# etapa1_suma.net
KiCad netlist of a schematic drawn in Altium Designer
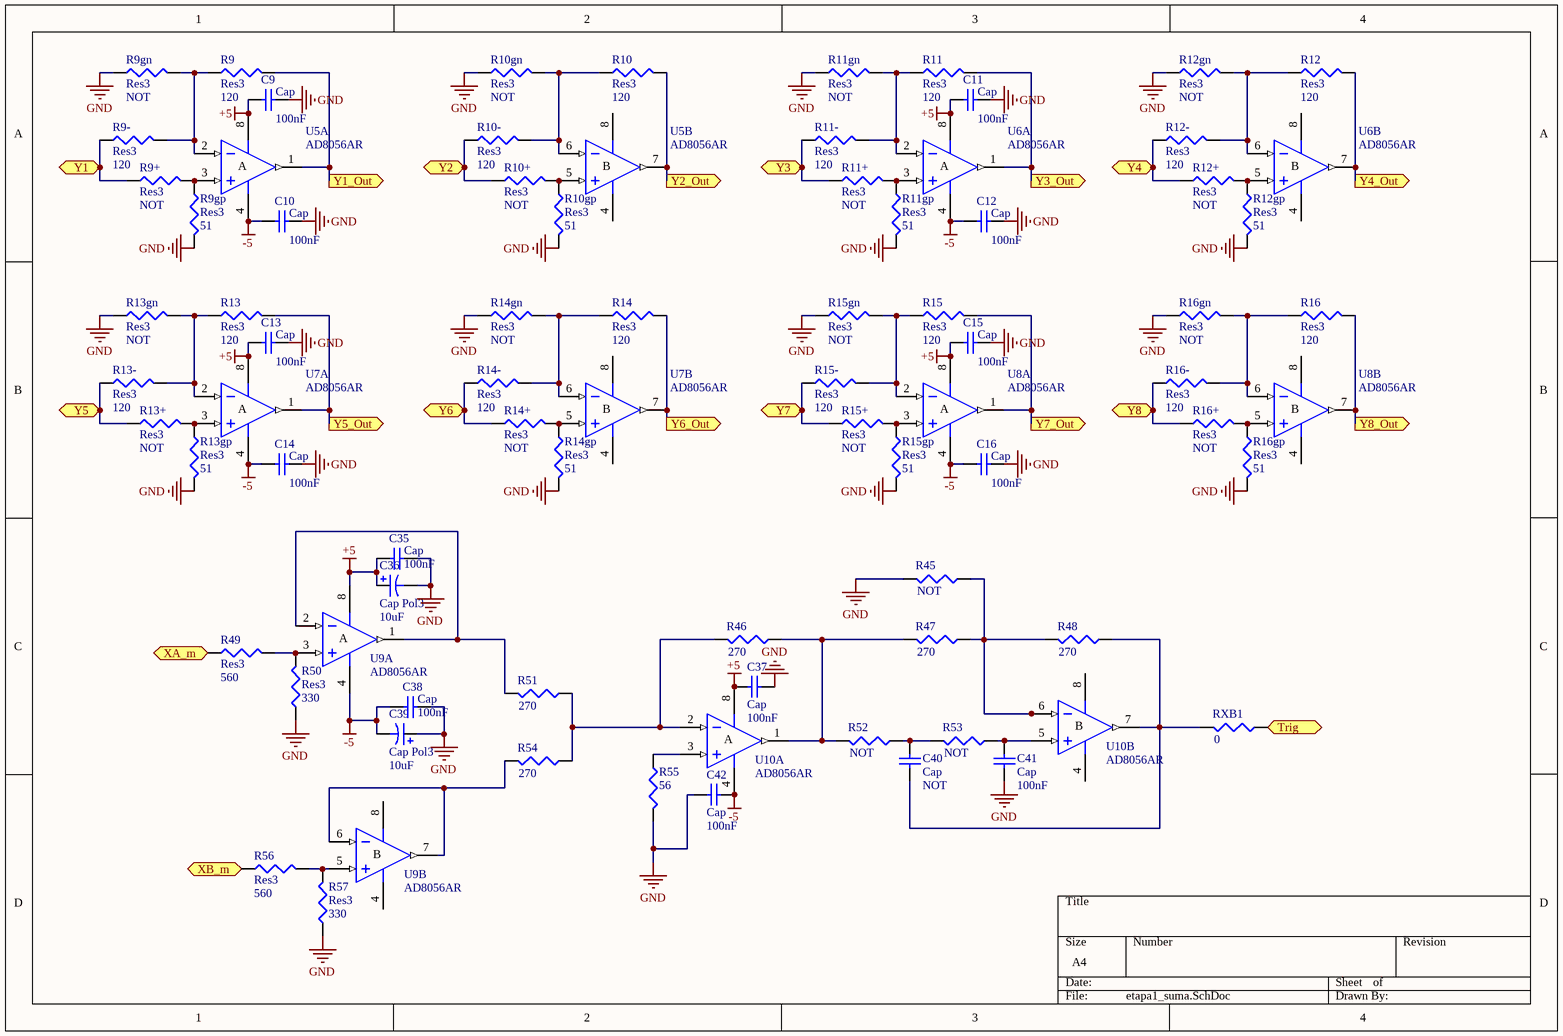
[diagram p0: etapa1_suma.SchDoc]

(export (version "E")
  (design (tool "Eeschema 10.0.6"))
  (components
    (comp (ref "C9")
      (value "Cap")
      (footprint "1608[0603]")
      (description "Capacitor")
      (fields (field (name "ALTIUM_VALUE") "100nF") (field (name "PUBLISHER") "Altium Limited"))
      (libsource (lib "Miscellaneous Devices") (part "Cap"))
    )
    (comp (ref "C10")
      (value "Cap")
      (footprint "1608[0603]")
      (description "Capacitor")
      (fields (field (name "ALTIUM_VALUE") "100nF") (field (name "PUBLISHER") "Altium Limited"))
      (libsource (lib "Miscellaneous Devices") (part "Cap"))
    )
    (comp (ref "C11")
      (value "Cap")
      (footprint "1608[0603]")
      (description "Capacitor")
      (fields (field (name "ALTIUM_VALUE") "100nF") (field (name "PUBLISHER") "Altium Limited"))
      (libsource (lib "Miscellaneous Devices") (part "Cap"))
    )
    (comp (ref "C12")
      (value "Cap")
      (footprint "1608[0603]")
      (description "Capacitor")
      (fields (field (name "ALTIUM_VALUE") "100nF") (field (name "PUBLISHER") "Altium Limited"))
      (libsource (lib "Miscellaneous Devices") (part "Cap"))
    )
    (comp (ref "C13")
      (value "Cap")
      (footprint "1608[0603]")
      (description "Capacitor")
      (fields (field (name "ALTIUM_VALUE") "100nF") (field (name "PUBLISHER") "Altium Limited"))
      (libsource (lib "Miscellaneous Devices") (part "Cap"))
    )
    (comp (ref "C14")
      (value "Cap")
      (footprint "1608[0603]")
      (description "Capacitor")
      (fields (field (name "ALTIUM_VALUE") "100nF") (field (name "PUBLISHER") "Altium Limited"))
      (libsource (lib "Miscellaneous Devices") (part "Cap"))
    )
    (comp (ref "C15")
      (value "Cap")
      (footprint "1608[0603]")
      (description "Capacitor")
      (fields (field (name "ALTIUM_VALUE") "100nF") (field (name "PUBLISHER") "Altium Limited"))
      (libsource (lib "Miscellaneous Devices") (part "Cap"))
    )
    (comp (ref "C16")
      (value "Cap")
      (footprint "1608[0603]")
      (description "Capacitor")
      (fields (field (name "ALTIUM_VALUE") "100nF") (field (name "PUBLISHER") "Altium Limited"))
      (libsource (lib "Miscellaneous Devices") (part "Cap"))
    )
    (comp (ref "C35")
      (value "Cap")
      (footprint "6-0805_N")
      (description "Capacitor")
      (fields (field (name "ALTIUM_VALUE") "100nF") (field (name "PUBLISHER") "Altium Limited"))
      (libsource (lib "Miscellaneous Devices") (part "Cap"))
    )
    (comp (ref "C36")
      (value "Cap Pol3")
      (footprint "6-0805_N")
      (description "Polarized Capacitor (Surface Mount)")
      (fields (field (name "ALTIUM_VALUE") "10uF") (field (name "PUBLISHER") "Altium Limited"))
      (libsource (lib "Miscellaneous Devices") (part "Cap Pol3"))
    )
    (comp (ref "C37")
      (value "Cap")
      (footprint "1608[0603]")
      (description "Capacitor")
      (fields (field (name "ALTIUM_VALUE") "100nF") (field (name "PUBLISHER") "Altium Limited"))
      (libsource (lib "Miscellaneous Devices") (part "Cap"))
    )
    (comp (ref "C38")
      (value "Cap")
      (footprint "6-0805_N")
      (description "Capacitor")
      (fields (field (name "ALTIUM_VALUE") "100nF") (field (name "PUBLISHER") "Altium Limited"))
      (libsource (lib "Miscellaneous Devices") (part "Cap"))
    )
    (comp (ref "C39")
      (value "Cap Pol3")
      (footprint "6-0805_N")
      (description "Polarized Capacitor (Surface Mount)")
      (fields (field (name "ALTIUM_VALUE") "10uF") (field (name "PUBLISHER") "Altium Limited"))
      (libsource (lib "Miscellaneous Devices") (part "Cap Pol3"))
    )
    (comp (ref "C40")
      (value "Cap")
      (footprint "1608[0603]")
      (description "Capacitor")
      (fields (field (name "ALTIUM_VALUE") "NOT") (field (name "PUBLISHER") "Altium Limited"))
      (libsource (lib "Miscellaneous Devices") (part "Cap"))
    )
    (comp (ref "C41")
      (value "Cap")
      (footprint "1608[0603]")
      (description "Capacitor")
      (fields (field (name "ALTIUM_VALUE") "100nF") (field (name "PUBLISHER") "Altium Limited"))
      (libsource (lib "Miscellaneous Devices") (part "Cap"))
    )
    (comp (ref "C42")
      (value "Cap")
      (footprint "1608[0603]")
      (description "Capacitor")
      (fields (field (name "ALTIUM_VALUE") "100nF") (field (name "PUBLISHER") "Altium Limited"))
      (libsource (lib "Miscellaneous Devices") (part "Cap"))
    )
    (comp (ref "R9")
      (value "Res3")
      (footprint "0402")
      (description "Resistor")
      (fields (field (name "ALTIUM_VALUE") "120") (field (name "PUBLISHER") "Altium Limited"))
      (libsource (lib "Miscellaneous Devices") (part "Res3"))
    )
    (comp (ref "R9+")
      (value "Res3")
      (footprint "0402")
      (description "Resistor")
      (fields (field (name "ALTIUM_VALUE") "NOT") (field (name "PUBLISHER") "Altium Limited"))
      (libsource (lib "Miscellaneous Devices") (part "Res3"))
    )
    (comp (ref "R9-")
      (value "Res3")
      (footprint "0402")
      (description "Resistor")
      (fields (field (name "ALTIUM_VALUE") "120") (field (name "PUBLISHER") "Altium Limited"))
      (libsource (lib "Miscellaneous Devices") (part "Res3"))
    )
    (comp (ref "R9gn")
      (value "Res3")
      (footprint "0402")
      (description "Resistor")
      (fields (field (name "ALTIUM_VALUE") "NOT") (field (name "PUBLISHER") "Altium Limited"))
      (libsource (lib "Miscellaneous Devices") (part "Res3"))
    )
    (comp (ref "R9gp")
      (value "Res3")
      (footprint "0402")
      (description "Resistor")
      (fields (field (name "ALTIUM_VALUE") "51") (field (name "PUBLISHER") "Altium Limited"))
      (libsource (lib "Miscellaneous Devices") (part "Res3"))
    )
    (comp (ref "R10")
      (value "Res3")
      (footprint "0402")
      (description "Resistor")
      (fields (field (name "ALTIUM_VALUE") "120") (field (name "PUBLISHER") "Altium Limited"))
      (libsource (lib "Miscellaneous Devices") (part "Res3"))
    )
    (comp (ref "R10+")
      (value "Res3")
      (footprint "0402")
      (description "Resistor")
      (fields (field (name "ALTIUM_VALUE") "NOT") (field (name "PUBLISHER") "Altium Limited"))
      (libsource (lib "Miscellaneous Devices") (part "Res3"))
    )
    (comp (ref "R10-")
      (value "Res3")
      (footprint "0402")
      (description "Resistor")
      (fields (field (name "ALTIUM_VALUE") "120") (field (name "PUBLISHER") "Altium Limited"))
      (libsource (lib "Miscellaneous Devices") (part "Res3"))
    )
    (comp (ref "R10gn")
      (value "Res3")
      (footprint "0402")
      (description "Resistor")
      (fields (field (name "ALTIUM_VALUE") "NOT") (field (name "PUBLISHER") "Altium Limited"))
      (libsource (lib "Miscellaneous Devices") (part "Res3"))
    )
    (comp (ref "R10gp")
      (value "Res3")
      (footprint "0402")
      (description "Resistor")
      (fields (field (name "ALTIUM_VALUE") "51") (field (name "PUBLISHER") "Altium Limited"))
      (libsource (lib "Miscellaneous Devices") (part "Res3"))
    )
    (comp (ref "R11")
      (value "Res3")
      (footprint "0402")
      (description "Resistor")
      (fields (field (name "ALTIUM_VALUE") "120") (field (name "PUBLISHER") "Altium Limited"))
      (libsource (lib "Miscellaneous Devices") (part "Res3"))
    )
    (comp (ref "R11+")
      (value "Res3")
      (footprint "0402")
      (description "Resistor")
      (fields (field (name "ALTIUM_VALUE") "NOT") (field (name "PUBLISHER") "Altium Limited"))
      (libsource (lib "Miscellaneous Devices") (part "Res3"))
    )
    (comp (ref "R11-")
      (value "Res3")
      (footprint "0402")
      (description "Resistor")
      (fields (field (name "ALTIUM_VALUE") "120") (field (name "PUBLISHER") "Altium Limited"))
      (libsource (lib "Miscellaneous Devices") (part "Res3"))
    )
    (comp (ref "R11gn")
      (value "Res3")
      (footprint "0402")
      (description "Resistor")
      (fields (field (name "ALTIUM_VALUE") "NOT") (field (name "PUBLISHER") "Altium Limited"))
      (libsource (lib "Miscellaneous Devices") (part "Res3"))
    )
    (comp (ref "R11gp")
      (value "Res3")
      (footprint "0402")
      (description "Resistor")
      (fields (field (name "ALTIUM_VALUE") "51") (field (name "PUBLISHER") "Altium Limited"))
      (libsource (lib "Miscellaneous Devices") (part "Res3"))
    )
    (comp (ref "R12")
      (value "Res3")
      (footprint "0402")
      (description "Resistor")
      (fields (field (name "ALTIUM_VALUE") "120") (field (name "PUBLISHER") "Altium Limited"))
      (libsource (lib "Miscellaneous Devices") (part "Res3"))
    )
    (comp (ref "R12+")
      (value "Res3")
      (footprint "0402")
      (description "Resistor")
      (fields (field (name "ALTIUM_VALUE") "NOT") (field (name "PUBLISHER") "Altium Limited"))
      (libsource (lib "Miscellaneous Devices") (part "Res3"))
    )
    (comp (ref "R12-")
      (value "Res3")
      (footprint "0402")
      (description "Resistor")
      (fields (field (name "ALTIUM_VALUE") "120") (field (name "PUBLISHER") "Altium Limited"))
      (libsource (lib "Miscellaneous Devices") (part "Res3"))
    )
    (comp (ref "R12gn")
      (value "Res3")
      (footprint "0402")
      (description "Resistor")
      (fields (field (name "ALTIUM_VALUE") "NOT") (field (name "PUBLISHER") "Altium Limited"))
      (libsource (lib "Miscellaneous Devices") (part "Res3"))
    )
    (comp (ref "R12gp")
      (value "Res3")
      (footprint "0402")
      (description "Resistor")
      (fields (field (name "ALTIUM_VALUE") "51") (field (name "PUBLISHER") "Altium Limited"))
      (libsource (lib "Miscellaneous Devices") (part "Res3"))
    )
    (comp (ref "R13")
      (value "Res3")
      (footprint "0402")
      (description "Resistor")
      (fields (field (name "ALTIUM_VALUE") "120") (field (name "PUBLISHER") "Altium Limited"))
      (libsource (lib "Miscellaneous Devices") (part "Res3"))
    )
    (comp (ref "R13+")
      (value "Res3")
      (footprint "0402")
      (description "Resistor")
      (fields (field (name "ALTIUM_VALUE") "NOT") (field (name "PUBLISHER") "Altium Limited"))
      (libsource (lib "Miscellaneous Devices") (part "Res3"))
    )
    (comp (ref "R13-")
      (value "Res3")
      (footprint "0402")
      (description "Resistor")
      (fields (field (name "ALTIUM_VALUE") "120") (field (name "PUBLISHER") "Altium Limited"))
      (libsource (lib "Miscellaneous Devices") (part "Res3"))
    )
    (comp (ref "R13gn")
      (value "Res3")
      (footprint "0402")
      (description "Resistor")
      (fields (field (name "ALTIUM_VALUE") "NOT") (field (name "PUBLISHER") "Altium Limited"))
      (libsource (lib "Miscellaneous Devices") (part "Res3"))
    )
    (comp (ref "R13gp")
      (value "Res3")
      (footprint "0402")
      (description "Resistor")
      (fields (field (name "ALTIUM_VALUE") "51") (field (name "PUBLISHER") "Altium Limited"))
      (libsource (lib "Miscellaneous Devices") (part "Res3"))
    )
    (comp (ref "R14")
      (value "Res3")
      (footprint "0402")
      (description "Resistor")
      (fields (field (name "ALTIUM_VALUE") "120") (field (name "PUBLISHER") "Altium Limited"))
      (libsource (lib "Miscellaneous Devices") (part "Res3"))
    )
    (comp (ref "R14+")
      (value "Res3")
      (footprint "0402")
      (description "Resistor")
      (fields (field (name "ALTIUM_VALUE") "NOT") (field (name "PUBLISHER") "Altium Limited"))
      (libsource (lib "Miscellaneous Devices") (part "Res3"))
    )
    (comp (ref "R14-")
      (value "Res3")
      (footprint "0402")
      (description "Resistor")
      (fields (field (name "ALTIUM_VALUE") "120") (field (name "PUBLISHER") "Altium Limited"))
      (libsource (lib "Miscellaneous Devices") (part "Res3"))
    )
    (comp (ref "R14gn")
      (value "Res3")
      (footprint "0402")
      (description "Resistor")
      (fields (field (name "ALTIUM_VALUE") "NOT") (field (name "PUBLISHER") "Altium Limited"))
      (libsource (lib "Miscellaneous Devices") (part "Res3"))
    )
    (comp (ref "R14gp")
      (value "Res3")
      (footprint "0402")
      (description "Resistor")
      (fields (field (name "ALTIUM_VALUE") "51") (field (name "PUBLISHER") "Altium Limited"))
      (libsource (lib "Miscellaneous Devices") (part "Res3"))
    )
    (comp (ref "R15")
      (value "Res3")
      (footprint "0402")
      (description "Resistor")
      (fields (field (name "ALTIUM_VALUE") "120") (field (name "PUBLISHER") "Altium Limited"))
      (libsource (lib "Miscellaneous Devices") (part "Res3"))
    )
    (comp (ref "R15+")
      (value "Res3")
      (footprint "0402")
      (description "Resistor")
      (fields (field (name "ALTIUM_VALUE") "NOT") (field (name "PUBLISHER") "Altium Limited"))
      (libsource (lib "Miscellaneous Devices") (part "Res3"))
    )
    (comp (ref "R15-")
      (value "Res3")
      (footprint "0402")
      (description "Resistor")
      (fields (field (name "ALTIUM_VALUE") "120") (field (name "PUBLISHER") "Altium Limited"))
      (libsource (lib "Miscellaneous Devices") (part "Res3"))
    )
    (comp (ref "R15gn")
      (value "Res3")
      (footprint "0402")
      (description "Resistor")
      (fields (field (name "ALTIUM_VALUE") "NOT") (field (name "PUBLISHER") "Altium Limited"))
      (libsource (lib "Miscellaneous Devices") (part "Res3"))
    )
    (comp (ref "R15gp")
      (value "Res3")
      (footprint "0402")
      (description "Resistor")
      (fields (field (name "ALTIUM_VALUE") "51") (field (name "PUBLISHER") "Altium Limited"))
      (libsource (lib "Miscellaneous Devices") (part "Res3"))
    )
    (comp (ref "R16")
      (value "Res3")
      (footprint "0402")
      (description "Resistor")
      (fields (field (name "ALTIUM_VALUE") "120") (field (name "PUBLISHER") "Altium Limited"))
      (libsource (lib "Miscellaneous Devices") (part "Res3"))
    )
    (comp (ref "R16+")
      (value "Res3")
      (footprint "0402")
      (description "Resistor")
      (fields (field (name "ALTIUM_VALUE") "NOT") (field (name "PUBLISHER") "Altium Limited"))
      (libsource (lib "Miscellaneous Devices") (part "Res3"))
    )
    (comp (ref "R16-")
      (value "Res3")
      (footprint "0402")
      (description "Resistor")
      (fields (field (name "ALTIUM_VALUE") "120") (field (name "PUBLISHER") "Altium Limited"))
      (libsource (lib "Miscellaneous Devices") (part "Res3"))
    )
    (comp (ref "R16gn")
      (value "Res3")
      (footprint "0402")
      (description "Resistor")
      (fields (field (name "ALTIUM_VALUE") "NOT") (field (name "PUBLISHER") "Altium Limited"))
      (libsource (lib "Miscellaneous Devices") (part "Res3"))
    )
    (comp (ref "R16gp")
      (value "Res3")
      (footprint "0402")
      (description "Resistor")
      (fields (field (name "ALTIUM_VALUE") "51") (field (name "PUBLISHER") "Altium Limited"))
      (libsource (lib "Miscellaneous Devices") (part "Res3"))
    )
    (comp (ref "R45")
      (value "NOT")
      (footprint "J1-0603")
      (description "Resistor")
      (fields (field (name "Comment") "Res3") (field (name "PUBLISHER") "Altium Limited"))
      (libsource (lib "Miscellaneous Devices") (part "Res3"))
    )
    (comp (ref "R46")
      (value "270")
      (footprint "J1-0603")
      (description "Resistor")
      (fields (field (name "Comment") "Res3") (field (name "PUBLISHER") "Altium Limited"))
      (libsource (lib "Miscellaneous Devices") (part "Res3"))
    )
    (comp (ref "R47")
      (value "270")
      (footprint "J1-0603")
      (description "Resistor")
      (fields (field (name "Comment") "Res3") (field (name "PUBLISHER") "Altium Limited"))
      (libsource (lib "Miscellaneous Devices") (part "Res3"))
    )
    (comp (ref "R48")
      (value "270")
      (footprint "J1-0603")
      (description "Resistor")
      (fields (field (name "Comment") "Res3") (field (name "PUBLISHER") "Altium Limited"))
      (libsource (lib "Miscellaneous Devices") (part "Res3"))
    )
    (comp (ref "R49")
      (value "Res3")
      (footprint "J1-0603")
      (description "Resistor")
      (fields (field (name "ALTIUM_VALUE") "560") (field (name "PUBLISHER") "Altium Limited"))
      (libsource (lib "Miscellaneous Devices") (part "Res3"))
    )
    (comp (ref "R50")
      (value "Res3")
      (footprint "J1-0603")
      (description "Resistor")
      (fields (field (name "ALTIUM_VALUE") "330") (field (name "PUBLISHER") "Altium Limited"))
      (libsource (lib "Miscellaneous Devices") (part "Res3"))
    )
    (comp (ref "R51")
      (value "270")
      (footprint "J1-0603")
      (description "Resistor")
      (fields (field (name "Comment") "Res3") (field (name "PUBLISHER") "Altium Limited"))
      (libsource (lib "Miscellaneous Devices") (part "Res3"))
    )
    (comp (ref "R52")
      (value "NOT")
      (footprint "J1-0603")
      (description "Resistor")
      (fields (field (name "Comment") "Res3") (field (name "PUBLISHER") "Altium Limited"))
      (libsource (lib "Miscellaneous Devices") (part "Res3"))
    )
    (comp (ref "R53")
      (value "NOT")
      (footprint "J1-0603")
      (description "Resistor")
      (fields (field (name "Comment") "Res3") (field (name "PUBLISHER") "Altium Limited"))
      (libsource (lib "Miscellaneous Devices") (part "Res3"))
    )
    (comp (ref "R54")
      (value "270")
      (footprint "J1-0603")
      (description "Resistor")
      (fields (field (name "Comment") "Res3") (field (name "PUBLISHER") "Altium Limited"))
      (libsource (lib "Miscellaneous Devices") (part "Res3"))
    )
    (comp (ref "R55")
      (value "56")
      (footprint "J1-0603")
      (description "Resistor")
      (fields (field (name "Comment") "Res3") (field (name "PUBLISHER") "Altium Limited"))
      (libsource (lib "Miscellaneous Devices") (part "Res3"))
    )
    (comp (ref "R56")
      (value "Res3")
      (footprint "J1-0603")
      (description "Resistor")
      (fields (field (name "ALTIUM_VALUE") "560") (field (name "PUBLISHER") "Altium Limited"))
      (libsource (lib "Miscellaneous Devices") (part "Res3"))
    )
    (comp (ref "R57")
      (value "Res3")
      (footprint "J1-0603")
      (description "Resistor")
      (fields (field (name "ALTIUM_VALUE") "330") (field (name "PUBLISHER") "Altium Limited"))
      (libsource (lib "Miscellaneous Devices") (part "Res3"))
    )
    (comp (ref "RXB1")
      (value "0")
      (footprint "J1-0603")
      (description "Resistor")
      (fields (field (name "Comment") "Res3") (field (name "PUBLISHER") "Altium Limited"))
      (libsource (lib "Miscellaneous Devices") (part "Res3"))
    )
    (comp (ref "U5")
      (value "AD8056AR")
      (footprint "RM-8")
      (description "Low Cost, 300MHz Voltage Feedback Amplifier")
      (fields (field (name "PUBLISHER") "Altium Limited"))
      (libsource (lib "AD Operational Amplifier") (part "AD8056AR"))
    )
    (comp (ref "U6")
      (value "AD8056AR")
      (footprint "RM-8")
      (description "Low Cost, 300MHz Voltage Feedback Amplifier")
      (fields (field (name "PUBLISHER") "Altium Limited"))
      (libsource (lib "AD Operational Amplifier") (part "AD8056AR"))
    )
    (comp (ref "U7")
      (value "AD8056AR")
      (footprint "RM-8")
      (description "Low Cost, 300MHz Voltage Feedback Amplifier")
      (fields (field (name "PUBLISHER") "Altium Limited"))
      (libsource (lib "AD Operational Amplifier") (part "AD8056AR"))
    )
    (comp (ref "U8")
      (value "AD8056AR")
      (footprint "RM-8")
      (description "Low Cost, 300MHz Voltage Feedback Amplifier")
      (fields (field (name "PUBLISHER") "Altium Limited"))
      (libsource (lib "AD Operational Amplifier") (part "AD8056AR"))
    )
    (comp (ref "U9")
      (value "AD8056AR")
      (footprint "RM-8")
      (description "Low Cost, 300MHz Voltage Feedback Amplifier")
      (fields (field (name "PUBLISHER") "Altium Limited"))
      (libsource (lib "AD Operational Amplifier") (part "AD8056AR"))
    )
    (comp (ref "U10")
      (value "AD8056AR")
      (footprint "RM-8")
      (description "Low Cost, 300MHz Voltage Feedback Amplifier")
      (fields (field (name "PUBLISHER") "Altium Limited"))
      (libsource (lib "AD Operational Amplifier") (part "AD8056AR"))
    )
  )
  (nets
    (net (code "1") (name "+5") (class "Default")
      (node (ref "C11") (pin "2") (pinfunction "2_2") (pintype "passive"))
      (node (ref "C13") (pin "2") (pinfunction "2_2") (pintype "passive"))
      (node (ref "C15") (pin "2") (pinfunction "2_2") (pintype "passive"))
      (node (ref "C35") (pin "2") (pinfunction "2_2") (pintype "passive"))
      (node (ref "C36") (pin "1") (pinfunction "1_1") (pintype "passive"))
      (node (ref "C37") (pin "1") (pinfunction "1_1") (pintype "passive"))
      (node (ref "C9") (pin "2") (pinfunction "2_2") (pintype "passive"))
      (node (ref "U10") (pin "8") (pinfunction "V+_8") (pintype "power_in"))
      (node (ref "U5") (pin "8") (pinfunction "V+_8") (pintype "power_in"))
      (node (ref "U6") (pin "8") (pinfunction "V+_8") (pintype "power_in"))
      (node (ref "U7") (pin "8") (pinfunction "V+_8") (pintype "power_in"))
      (node (ref "U8") (pin "8") (pinfunction "V+_8") (pintype "power_in"))
      (node (ref "U9") (pin "8") (pinfunction "V+_8") (pintype "power_in"))
    )
    (net (code "2") (name "-5") (class "Default")
      (node (ref "C10") (pin "2") (pinfunction "2_2") (pintype "passive"))
      (node (ref "C12") (pin "2") (pinfunction "2_2") (pintype "passive"))
      (node (ref "C14") (pin "2") (pinfunction "2_2") (pintype "passive"))
      (node (ref "C16") (pin "2") (pinfunction "2_2") (pintype "passive"))
      (node (ref "C38") (pin "2") (pinfunction "2_2") (pintype "passive"))
      (node (ref "C39") (pin "2") (pinfunction "2_2") (pintype "passive"))
      (node (ref "C42") (pin "2") (pinfunction "2_2") (pintype "passive"))
      (node (ref "U10") (pin "4") (pinfunction "V-_4") (pintype "power_in"))
      (node (ref "U5") (pin "4") (pinfunction "V-_4") (pintype "power_in"))
      (node (ref "U6") (pin "4") (pinfunction "V-_4") (pintype "power_in"))
      (node (ref "U7") (pin "4") (pinfunction "V-_4") (pintype "power_in"))
      (node (ref "U8") (pin "4") (pinfunction "V-_4") (pintype "power_in"))
      (node (ref "U9") (pin "4") (pinfunction "V-_4") (pintype "power_in"))
    )
    (net (code "3") (name "/Trig") (class "Default")
      (node (ref "RXB1") (pin "1") (pinfunction "1_1") (pintype "passive"))
    )
    (net (code "4") (name "/XA_m") (class "Default")
      (node (ref "R49") (pin "1") (pinfunction "1_1") (pintype "passive"))
    )
    (net (code "5") (name "/XB_m") (class "Default")
      (node (ref "R56") (pin "1") (pinfunction "1_1") (pintype "passive"))
    )
    (net (code "6") (name "/Y1") (class "Default")
      (node (ref "R9+") (pin "1") (pinfunction "1_1") (pintype "passive"))
      (node (ref "R9-") (pin "1") (pinfunction "1_1") (pintype "passive"))
    )
    (net (code "7") (name "/Y1_Out") (class "Default")
      (node (ref "R9") (pin "2") (pinfunction "2_2") (pintype "passive"))
      (node (ref "U5") (pin "1") (pinfunction "OUT_1") (pintype "output"))
    )
    (net (code "8") (name "/Y2") (class "Default")
      (node (ref "R10+") (pin "1") (pinfunction "1_1") (pintype "passive"))
      (node (ref "R10-") (pin "1") (pinfunction "1_1") (pintype "passive"))
    )
    (net (code "9") (name "/Y2_Out") (class "Default")
      (node (ref "R10") (pin "2") (pinfunction "2_2") (pintype "passive"))
      (node (ref "U5") (pin "7") (pinfunction "OUT_7") (pintype "output"))
    )
    (net (code "10") (name "/Y3") (class "Default")
      (node (ref "R11+") (pin "1") (pinfunction "1_1") (pintype "passive"))
      (node (ref "R11-") (pin "1") (pinfunction "1_1") (pintype "passive"))
    )
    (net (code "11") (name "/Y3_Out") (class "Default")
      (node (ref "R11") (pin "2") (pinfunction "2_2") (pintype "passive"))
      (node (ref "U6") (pin "1") (pinfunction "OUT_1") (pintype "output"))
    )
    (net (code "12") (name "/Y4") (class "Default")
      (node (ref "R12+") (pin "1") (pinfunction "1_1") (pintype "passive"))
      (node (ref "R12-") (pin "1") (pinfunction "1_1") (pintype "passive"))
    )
    (net (code "13") (name "/Y4_Out") (class "Default")
      (node (ref "R12") (pin "2") (pinfunction "2_2") (pintype "passive"))
      (node (ref "U6") (pin "7") (pinfunction "OUT_7") (pintype "output"))
    )
    (net (code "14") (name "/Y5") (class "Default")
      (node (ref "R13+") (pin "1") (pinfunction "1_1") (pintype "passive"))
      (node (ref "R13-") (pin "1") (pinfunction "1_1") (pintype "passive"))
    )
    (net (code "15") (name "/Y5_Out") (class "Default")
      (node (ref "R13") (pin "2") (pinfunction "2_2") (pintype "passive"))
      (node (ref "U7") (pin "1") (pinfunction "OUT_1") (pintype "output"))
    )
    (net (code "16") (name "/Y6") (class "Default")
      (node (ref "R14+") (pin "1") (pinfunction "1_1") (pintype "passive"))
      (node (ref "R14-") (pin "1") (pinfunction "1_1") (pintype "passive"))
    )
    (net (code "17") (name "/Y6_Out") (class "Default")
      (node (ref "R14") (pin "2") (pinfunction "2_2") (pintype "passive"))
      (node (ref "U7") (pin "7") (pinfunction "OUT_7") (pintype "output"))
    )
    (net (code "18") (name "/Y7") (class "Default")
      (node (ref "R15+") (pin "1") (pinfunction "1_1") (pintype "passive"))
      (node (ref "R15-") (pin "1") (pinfunction "1_1") (pintype "passive"))
    )
    (net (code "19") (name "/Y7_Out") (class "Default")
      (node (ref "R15") (pin "2") (pinfunction "2_2") (pintype "passive"))
      (node (ref "U8") (pin "1") (pinfunction "OUT_1") (pintype "output"))
    )
    (net (code "20") (name "/Y8") (class "Default")
      (node (ref "R16+") (pin "1") (pinfunction "1_1") (pintype "passive"))
      (node (ref "R16-") (pin "1") (pinfunction "1_1") (pintype "passive"))
    )
    (net (code "21") (name "/Y8_Out") (class "Default")
      (node (ref "R16") (pin "2") (pinfunction "2_2") (pintype "passive"))
      (node (ref "U8") (pin "7") (pinfunction "OUT_7") (pintype "output"))
    )
    (net (code "22") (name "GND") (class "Default")
      (node (ref "C10") (pin "1") (pinfunction "1_1") (pintype "passive"))
      (node (ref "C11") (pin "1") (pinfunction "1_1") (pintype "passive"))
      (node (ref "C12") (pin "1") (pinfunction "1_1") (pintype "passive"))
      (node (ref "C13") (pin "1") (pinfunction "1_1") (pintype "passive"))
      (node (ref "C14") (pin "1") (pinfunction "1_1") (pintype "passive"))
      (node (ref "C15") (pin "1") (pinfunction "1_1") (pintype "passive"))
      (node (ref "C16") (pin "1") (pinfunction "1_1") (pintype "passive"))
      (node (ref "C35") (pin "1") (pinfunction "1_1") (pintype "passive"))
      (node (ref "C36") (pin "2") (pinfunction "2_2") (pintype "passive"))
      (node (ref "C37") (pin "2") (pinfunction "2_2") (pintype "passive"))
      (node (ref "C38") (pin "1") (pinfunction "1_1") (pintype "passive"))
      (node (ref "C39") (pin "1") (pinfunction "1_1") (pintype "passive"))
      (node (ref "C41") (pin "2") (pinfunction "2_2") (pintype "passive"))
      (node (ref "C42") (pin "1") (pinfunction "1_1") (pintype "passive"))
      (node (ref "C9") (pin "1") (pinfunction "1_1") (pintype "passive"))
      (node (ref "R10gn") (pin "1") (pinfunction "1_1") (pintype "passive"))
      (node (ref "R10gp") (pin "2") (pinfunction "2_2") (pintype "passive"))
      (node (ref "R11gn") (pin "1") (pinfunction "1_1") (pintype "passive"))
      (node (ref "R11gp") (pin "2") (pinfunction "2_2") (pintype "passive"))
      (node (ref "R12gn") (pin "1") (pinfunction "1_1") (pintype "passive"))
      (node (ref "R12gp") (pin "2") (pinfunction "2_2") (pintype "passive"))
      (node (ref "R13gn") (pin "1") (pinfunction "1_1") (pintype "passive"))
      (node (ref "R13gp") (pin "2") (pinfunction "2_2") (pintype "passive"))
      (node (ref "R14gn") (pin "1") (pinfunction "1_1") (pintype "passive"))
      (node (ref "R14gp") (pin "2") (pinfunction "2_2") (pintype "passive"))
      (node (ref "R15gn") (pin "1") (pinfunction "1_1") (pintype "passive"))
      (node (ref "R15gp") (pin "2") (pinfunction "2_2") (pintype "passive"))
      (node (ref "R16gn") (pin "1") (pinfunction "1_1") (pintype "passive"))
      (node (ref "R16gp") (pin "2") (pinfunction "2_2") (pintype "passive"))
      (node (ref "R45") (pin "2") (pinfunction "2_2") (pintype "passive"))
      (node (ref "R50") (pin "1") (pinfunction "1_1") (pintype "passive"))
      (node (ref "R55") (pin "2") (pinfunction "2_2") (pintype "passive"))
      (node (ref "R57") (pin "1") (pinfunction "1_1") (pintype "passive"))
      (node (ref "R9gn") (pin "1") (pinfunction "1_1") (pintype "passive"))
      (node (ref "R9gp") (pin "2") (pinfunction "2_2") (pintype "passive"))
    )
    (net (code "23") (name "Net-(C40-Pad1)") (class "Default")
      (node (ref "C40") (pin "1") (pinfunction "1_1") (pintype "passive"))
      (node (ref "R52") (pin "1") (pinfunction "1_1") (pintype "passive"))
      (node (ref "R53") (pin "2") (pinfunction "2_2") (pintype "passive"))
    )
    (net (code "24") (name "Net-(U5A-IN+)") (class "Default")
      (node (ref "R9+") (pin "2") (pinfunction "2_2") (pintype "passive"))
      (node (ref "R9gp") (pin "1") (pinfunction "1_1") (pintype "passive"))
      (node (ref "U5") (pin "3") (pinfunction "IN+_3") (pintype "input"))
    )
    (net (code "25") (name "Net-(U5A-IN-)") (class "Default")
      (node (ref "R9") (pin "1") (pinfunction "1_1") (pintype "passive"))
      (node (ref "R9-") (pin "2") (pinfunction "2_2") (pintype "passive"))
      (node (ref "R9gn") (pin "2") (pinfunction "2_2") (pintype "passive"))
      (node (ref "U5") (pin "2") (pinfunction "IN-_2") (pintype "input"))
    )
    (net (code "26") (name "Net-(U5B-IN+)") (class "Default")
      (node (ref "R10+") (pin "2") (pinfunction "2_2") (pintype "passive"))
      (node (ref "R10gp") (pin "1") (pinfunction "1_1") (pintype "passive"))
      (node (ref "U5") (pin "5") (pinfunction "IN+_5") (pintype "input"))
    )
    (net (code "27") (name "Net-(U5B-IN-)") (class "Default")
      (node (ref "R10") (pin "1") (pinfunction "1_1") (pintype "passive"))
      (node (ref "R10-") (pin "2") (pinfunction "2_2") (pintype "passive"))
      (node (ref "R10gn") (pin "2") (pinfunction "2_2") (pintype "passive"))
      (node (ref "U5") (pin "6") (pinfunction "IN-_6") (pintype "input"))
    )
    (net (code "28") (name "Net-(U6A-IN+)") (class "Default")
      (node (ref "R11+") (pin "2") (pinfunction "2_2") (pintype "passive"))
      (node (ref "R11gp") (pin "1") (pinfunction "1_1") (pintype "passive"))
      (node (ref "U6") (pin "3") (pinfunction "IN+_3") (pintype "input"))
    )
    (net (code "29") (name "Net-(U6A-IN-)") (class "Default")
      (node (ref "R11") (pin "1") (pinfunction "1_1") (pintype "passive"))
      (node (ref "R11-") (pin "2") (pinfunction "2_2") (pintype "passive"))
      (node (ref "R11gn") (pin "2") (pinfunction "2_2") (pintype "passive"))
      (node (ref "U6") (pin "2") (pinfunction "IN-_2") (pintype "input"))
    )
    (net (code "30") (name "Net-(U6B-IN+)") (class "Default")
      (node (ref "R12+") (pin "2") (pinfunction "2_2") (pintype "passive"))
      (node (ref "R12gp") (pin "1") (pinfunction "1_1") (pintype "passive"))
      (node (ref "U6") (pin "5") (pinfunction "IN+_5") (pintype "input"))
    )
    (net (code "31") (name "Net-(U6B-IN-)") (class "Default")
      (node (ref "R12") (pin "1") (pinfunction "1_1") (pintype "passive"))
      (node (ref "R12-") (pin "2") (pinfunction "2_2") (pintype "passive"))
      (node (ref "R12gn") (pin "2") (pinfunction "2_2") (pintype "passive"))
      (node (ref "U6") (pin "6") (pinfunction "IN-_6") (pintype "input"))
    )
    (net (code "32") (name "Net-(U7A-IN+)") (class "Default")
      (node (ref "R13+") (pin "2") (pinfunction "2_2") (pintype "passive"))
      (node (ref "R13gp") (pin "1") (pinfunction "1_1") (pintype "passive"))
      (node (ref "U7") (pin "3") (pinfunction "IN+_3") (pintype "input"))
    )
    (net (code "33") (name "Net-(U7A-IN-)") (class "Default")
      (node (ref "R13") (pin "1") (pinfunction "1_1") (pintype "passive"))
      (node (ref "R13-") (pin "2") (pinfunction "2_2") (pintype "passive"))
      (node (ref "R13gn") (pin "2") (pinfunction "2_2") (pintype "passive"))
      (node (ref "U7") (pin "2") (pinfunction "IN-_2") (pintype "input"))
    )
    (net (code "34") (name "Net-(U7B-IN+)") (class "Default")
      (node (ref "R14+") (pin "2") (pinfunction "2_2") (pintype "passive"))
      (node (ref "R14gp") (pin "1") (pinfunction "1_1") (pintype "passive"))
      (node (ref "U7") (pin "5") (pinfunction "IN+_5") (pintype "input"))
    )
    (net (code "35") (name "Net-(U7B-IN-)") (class "Default")
      (node (ref "R14") (pin "1") (pinfunction "1_1") (pintype "passive"))
      (node (ref "R14-") (pin "2") (pinfunction "2_2") (pintype "passive"))
      (node (ref "R14gn") (pin "2") (pinfunction "2_2") (pintype "passive"))
      (node (ref "U7") (pin "6") (pinfunction "IN-_6") (pintype "input"))
    )
    (net (code "36") (name "Net-(U8A-IN+)") (class "Default")
      (node (ref "R15+") (pin "2") (pinfunction "2_2") (pintype "passive"))
      (node (ref "R15gp") (pin "1") (pinfunction "1_1") (pintype "passive"))
      (node (ref "U8") (pin "3") (pinfunction "IN+_3") (pintype "input"))
    )
    (net (code "37") (name "Net-(U8A-IN-)") (class "Default")
      (node (ref "R15") (pin "1") (pinfunction "1_1") (pintype "passive"))
      (node (ref "R15-") (pin "2") (pinfunction "2_2") (pintype "passive"))
      (node (ref "R15gn") (pin "2") (pinfunction "2_2") (pintype "passive"))
      (node (ref "U8") (pin "2") (pinfunction "IN-_2") (pintype "input"))
    )
    (net (code "38") (name "Net-(U8B-IN+)") (class "Default")
      (node (ref "R16+") (pin "2") (pinfunction "2_2") (pintype "passive"))
      (node (ref "R16gp") (pin "1") (pinfunction "1_1") (pintype "passive"))
      (node (ref "U8") (pin "5") (pinfunction "IN+_5") (pintype "input"))
    )
    (net (code "39") (name "Net-(U8B-IN-)") (class "Default")
      (node (ref "R16") (pin "1") (pinfunction "1_1") (pintype "passive"))
      (node (ref "R16-") (pin "2") (pinfunction "2_2") (pintype "passive"))
      (node (ref "R16gn") (pin "2") (pinfunction "2_2") (pintype "passive"))
      (node (ref "U8") (pin "6") (pinfunction "IN-_6") (pintype "input"))
    )
    (net (code "40") (name "Net-(U9A-IN+)") (class "Default")
      (node (ref "R49") (pin "2") (pinfunction "2_2") (pintype "passive"))
      (node (ref "R50") (pin "2") (pinfunction "2_2") (pintype "passive"))
      (node (ref "U9") (pin "3") (pinfunction "IN+_3") (pintype "input"))
    )
    (net (code "41") (name "Net-(U9A-IN-)") (class "Default")
      (node (ref "R51") (pin "2") (pinfunction "2_2") (pintype "passive"))
      (node (ref "U9") (pin "1") (pinfunction "OUT_1") (pintype "output"))
      (node (ref "U9") (pin "2") (pinfunction "IN-_2") (pintype "input"))
    )
    (net (code "42") (name "Net-(U9B-IN+)") (class "Default")
      (node (ref "R56") (pin "2") (pinfunction "2_2") (pintype "passive"))
      (node (ref "R57") (pin "2") (pinfunction "2_2") (pintype "passive"))
      (node (ref "U9") (pin "5") (pinfunction "IN+_5") (pintype "input"))
    )
    (net (code "43") (name "Net-(U9B-IN-)") (class "Default")
      (node (ref "R54") (pin "2") (pinfunction "2_2") (pintype "passive"))
      (node (ref "U9") (pin "6") (pinfunction "IN-_6") (pintype "input"))
      (node (ref "U9") (pin "7") (pinfunction "OUT_7") (pintype "output"))
    )
    (net (code "44") (name "Net-(U10A-IN+)") (class "Default")
      (node (ref "R55") (pin "1") (pinfunction "1_1") (pintype "passive"))
      (node (ref "U10") (pin "3") (pinfunction "IN+_3") (pintype "input"))
    )
    (net (code "45") (name "Net-(U10A-IN-)") (class "Default")
      (node (ref "R46") (pin "2") (pinfunction "2_2") (pintype "passive"))
      (node (ref "R51") (pin "1") (pinfunction "1_1") (pintype "passive"))
      (node (ref "R54") (pin "1") (pinfunction "1_1") (pintype "passive"))
      (node (ref "U10") (pin "2") (pinfunction "IN-_2") (pintype "input"))
    )
    (net (code "46") (name "Net-(U10A-OUT)") (class "Default")
      (node (ref "R46") (pin "1") (pinfunction "1_1") (pintype "passive"))
      (node (ref "R47") (pin "2") (pinfunction "2_2") (pintype "passive"))
      (node (ref "R52") (pin "2") (pinfunction "2_2") (pintype "passive"))
      (node (ref "U10") (pin "1") (pinfunction "OUT_1") (pintype "output"))
    )
    (net (code "47") (name "Net-(U10B-IN+)") (class "Default")
      (node (ref "C41") (pin "1") (pinfunction "1_1") (pintype "passive"))
      (node (ref "R53") (pin "1") (pinfunction "1_1") (pintype "passive"))
      (node (ref "U10") (pin "5") (pinfunction "IN+_5") (pintype "input"))
    )
    (net (code "48") (name "Net-(U10B-IN-)") (class "Default")
      (node (ref "R45") (pin "1") (pinfunction "1_1") (pintype "passive"))
      (node (ref "R47") (pin "1") (pinfunction "1_1") (pintype "passive"))
      (node (ref "R48") (pin "2") (pinfunction "2_2") (pintype "passive"))
      (node (ref "U10") (pin "6") (pinfunction "IN-_6") (pintype "input"))
    )
    (net (code "49") (name "Net-(U10B-OUT)") (class "Default")
      (node (ref "C40") (pin "2") (pinfunction "2_2") (pintype "passive"))
      (node (ref "R48") (pin "1") (pinfunction "1_1") (pintype "passive"))
      (node (ref "RXB1") (pin "2") (pinfunction "2_2") (pintype "passive"))
      (node (ref "U10") (pin "7") (pinfunction "OUT_7") (pintype "output"))
    )
    (net (code "50") (name "unconnected-(U5B-V+-Pad8)") (class "Default")
      (node (ref "U5") (pin "8") (pinfunction "V+_8") (pintype "power_in"))
    )
    (net (code "51") (name "unconnected-(U5B-V--Pad4)") (class "Default")
      (node (ref "U5") (pin "4") (pinfunction "V-_4") (pintype "power_in"))
    )
    (net (code "52") (name "unconnected-(U6B-V+-Pad8)") (class "Default")
      (node (ref "U6") (pin "8") (pinfunction "V+_8") (pintype "power_in"))
    )
    (net (code "53") (name "unconnected-(U6B-V--Pad4)") (class "Default")
      (node (ref "U6") (pin "4") (pinfunction "V-_4") (pintype "power_in"))
    )
    (net (code "54") (name "unconnected-(U7B-V+-Pad8)") (class "Default")
      (node (ref "U7") (pin "8") (pinfunction "V+_8") (pintype "power_in"))
    )
    (net (code "55") (name "unconnected-(U7B-V--Pad4)") (class "Default")
      (node (ref "U7") (pin "4") (pinfunction "V-_4") (pintype "power_in"))
    )
    (net (code "56") (name "unconnected-(U8B-V+-Pad8)") (class "Default")
      (node (ref "U8") (pin "8") (pinfunction "V+_8") (pintype "power_in"))
    )
    (net (code "57") (name "unconnected-(U8B-V--Pad4)") (class "Default")
      (node (ref "U8") (pin "4") (pinfunction "V-_4") (pintype "power_in"))
    )
    (net (code "58") (name "unconnected-(U9B-V+-Pad8)") (class "Default")
      (node (ref "U9") (pin "8") (pinfunction "V+_8") (pintype "power_in"))
    )
    (net (code "59") (name "unconnected-(U9B-V--Pad4)") (class "Default")
      (node (ref "U9") (pin "4") (pinfunction "V-_4") (pintype "power_in"))
    )
    (net (code "60") (name "unconnected-(U10B-V+-Pad8)") (class "Default")
      (node (ref "U10") (pin "8") (pinfunction "V+_8") (pintype "power_in"))
    )
    (net (code "61") (name "unconnected-(U10B-V--Pad4)") (class "Default")
      (node (ref "U10") (pin "4") (pinfunction "V-_4") (pintype "power_in"))
    )
  )
)
